# MQ.net
KiCad netlist of a schematic drawn in EAGLE
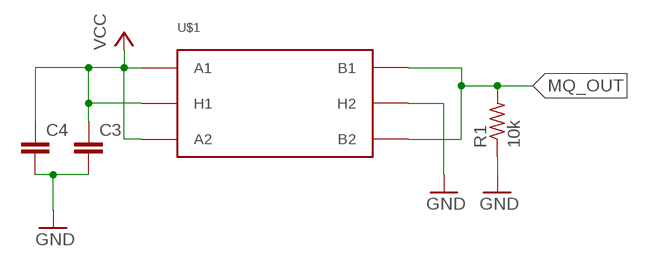
[diagram p0: schematic, sheet 1]

(export (version "E")
  (design (tool "Eeschema 10.0.6"))
  (components
    (comp (ref "C3")
      (value "C-EUC0603")
      (footprint "eagle-import:C0603")
      (libsource (lib "eagle-import") (part "C-EUC0603"))
    )
    (comp (ref "C4")
      (value "C-EUC0603")
      (footprint "eagle-import:C0603")
      (libsource (lib "eagle-import") (part "C-EUC0603"))
    )
    (comp (ref "R1")
      (value "10k")
      (footprint "eagle-import:R0603")
      (libsource (lib "eagle-import") (part "R-US_R0603"))
    )
    (comp (ref "U$1")
      (value "MQ_GAS_SENSOR_SOCKET")
      (footprint "eagle-import:GAS_SENSOR_SOCKET")
      (libsource (lib "eagle-import") (part "MQ_GAS_SENSOR_SOCKET"))
    )
  )
  (nets
    (net (code "1") (name "GND") (class "Default")
      (node (ref "C3") (pin "2") (pinfunction "2_2") (pintype "passive"))
      (node (ref "C4") (pin "2") (pinfunction "2_2") (pintype "passive"))
      (node (ref "R1") (pin "1") (pinfunction "1_1") (pintype "passive"))
      (node (ref "U$1") (pin "H2") (pinfunction "H2_H2") (pintype "bidirectional"))
      (node (ref "U$1") (pin "H22") (pinfunction "H2_H22") (pintype "bidirectional"))
    )
    (net (code "2") (name "MQ_OUT") (class "Default")
      (node (ref "R1") (pin "2") (pinfunction "2_2") (pintype "passive"))
      (node (ref "U$1") (pin "B1") (pinfunction "B1_B1") (pintype "bidirectional"))
      (node (ref "U$1") (pin "B11") (pinfunction "B1_B11") (pintype "bidirectional"))
      (node (ref "U$1") (pin "B2") (pinfunction "B2_B2") (pintype "bidirectional"))
      (node (ref "U$1") (pin "B22") (pinfunction "B2_B22") (pintype "bidirectional"))
    )
    (net (code "3") (name "VCC") (class "Default")
      (node (ref "C3") (pin "1") (pinfunction "1_1") (pintype "passive"))
      (node (ref "C4") (pin "1") (pinfunction "1_1") (pintype "passive"))
      (node (ref "U$1") (pin "A1") (pinfunction "A1_A1") (pintype "bidirectional"))
      (node (ref "U$1") (pin "A11") (pinfunction "A1_A11") (pintype "bidirectional"))
      (node (ref "U$1") (pin "A2") (pinfunction "A2_A2") (pintype "bidirectional"))
      (node (ref "U$1") (pin "A22") (pinfunction "A2_A22") (pintype "bidirectional"))
      (node (ref "U$1") (pin "H1") (pinfunction "H1_H1") (pintype "bidirectional"))
      (node (ref "U$1") (pin "H11") (pinfunction "H1_H11") (pintype "bidirectional"))
    )
  )
)
